# SCH_TCKF-NFC-Card_2024-09-04.net
KiCad netlist of a schematic drawn in EasyEDA
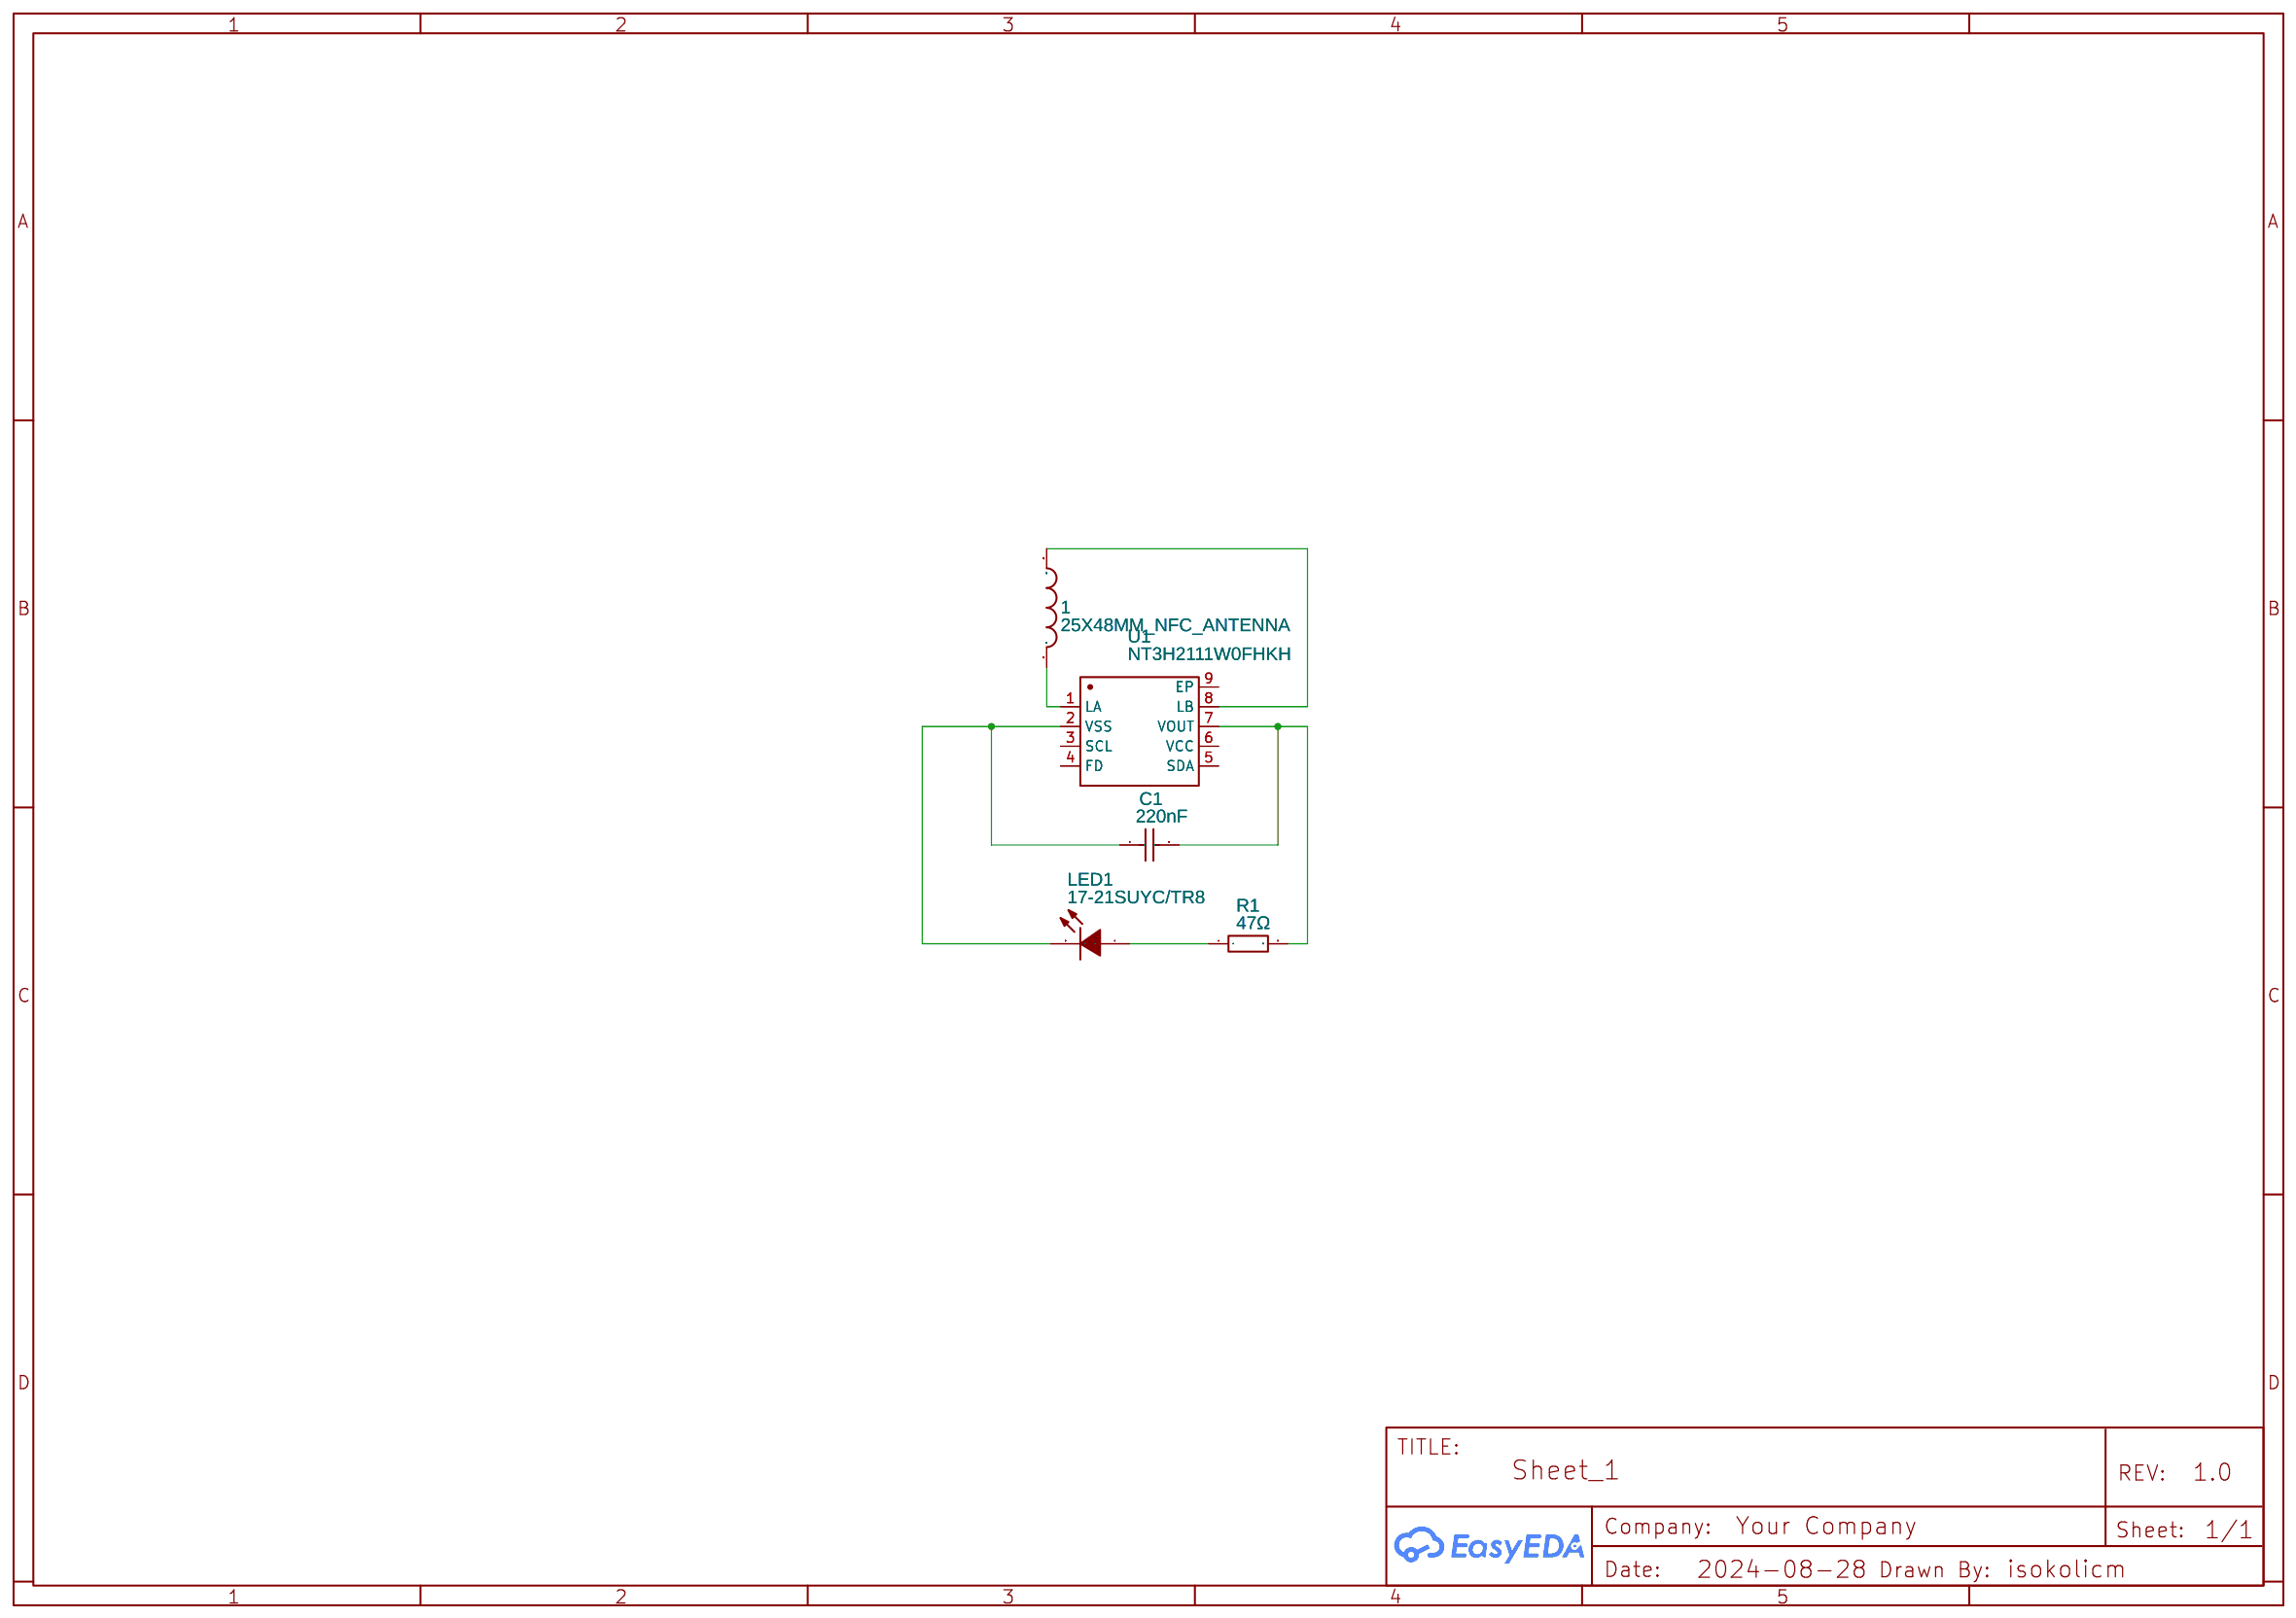
[diagram p0: schematic sheet]

(export (version "E")
  (design (tool "Eeschema 10.0.6"))
  (components
    (comp (ref "1") (value "25X48MM_NFC_ANTENNA") (libsource (lib "") (part "25X48MM_NFC_ANTENNA")))
    (comp (ref "C1")
      (value "220nF")
      (fields
        (field (name "Manufacturer Part") "CL10B224KA8NNNC")
        (field (name "Manufacturer") "SAMSUNG(三星)")
      )
      (libsource (lib "") (part "CL10B224KA8NNNC"))
    )
    (comp (ref "LED1")
      (value "17-21SUYC/TR8")
      (fields (field (name "Manufacturer Part") "KT-0805黄灯") (field (name "Manufacturer") "KENTO"))
      (libsource (lib "") (part "17-21SUYC/TR8"))
    )
    (comp (ref "R1")
      (value "47Ω")
      (fields
        (field (name "Manufacturer Part") "0603WAF470JT5E")
        (field (name "Manufacturer") "UNI-ROYAL(厚声)")
      )
      (libsource (lib "") (part "0603WAF470JT5E"))
    )
    (comp (ref "U1")
      (value "NT3H2111W0FHKH")
      (fields (field (name "Manufacturer") "NXP(恩智浦)"))
      (libsource (lib "") (part "NT3H2111W0FHKH"))
    )
  )
  (nets
    (net (code "1") (name "Net-(LED1-+)") (class "Default")
      (node (ref "LED1") (pin "1") (pinfunction "+_1") (pintype "unspecified"))
      (node (ref "R1") (pin "1") (pinfunction "1_1") (pintype "input"))
    )
    (net (code "2") (name "Net-(LED1--)") (class "Default")
      (node (ref "C1") (pin "1") (pinfunction "1_1") (pintype "input"))
      (node (ref "LED1") (pin "2") (pinfunction "-_2") (pintype "unspecified"))
      (node (ref "U1") (pin "2") (pinfunction "VSS_2") (pintype "unspecified"))
    )
    (net (code "3") (name "Net-(U1-LA)") (class "Default")
      (node (ref "1") (pin "P$2") (pinfunction "P$2_P$2") (pintype "bidirectional"))
      (node (ref "U1") (pin "1") (pinfunction "LA_1") (pintype "unspecified"))
    )
    (net (code "4") (name "Net-(U1-LB)") (class "Default")
      (node (ref "1") (pin "P$1") (pinfunction "P$1_P$1") (pintype "bidirectional"))
      (node (ref "U1") (pin "8") (pinfunction "LB_8") (pintype "unspecified"))
    )
    (net (code "5") (name "Net-(U1-VOUT)") (class "Default")
      (node (ref "C1") (pin "2") (pinfunction "2_2") (pintype "input"))
      (node (ref "R1") (pin "2") (pinfunction "2_2") (pintype "input"))
      (node (ref "U1") (pin "7") (pinfunction "VOUT_7") (pintype "unspecified"))
    )
    (net (code "6") (name "unconnected-(U1-EP-Pad9)") (class "Default")
      (node (ref "U1") (pin "9") (pinfunction "EP_9") (pintype "unspecified"))
    )
    (net (code "7") (name "unconnected-(U1-FD-Pad4)") (class "Default")
      (node (ref "U1") (pin "4") (pinfunction "FD_4") (pintype "unspecified"))
    )
    (net (code "8") (name "unconnected-(U1-SCL-Pad3)") (class "Default")
      (node (ref "U1") (pin "3") (pinfunction "SCL_3") (pintype "unspecified"))
    )
    (net (code "9") (name "unconnected-(U1-SDA-Pad5)") (class "Default")
      (node (ref "U1") (pin "5") (pinfunction "SDA_5") (pintype "unspecified"))
    )
    (net (code "10") (name "unconnected-(U1-VCC-Pad6)") (class "Default")
      (node (ref "U1") (pin "6") (pinfunction "VCC_6") (pintype "unspecified"))
    )
  )
)
